# amplificadorAudio.net
KiCad netlist of a schematic drawn in Altium Designer
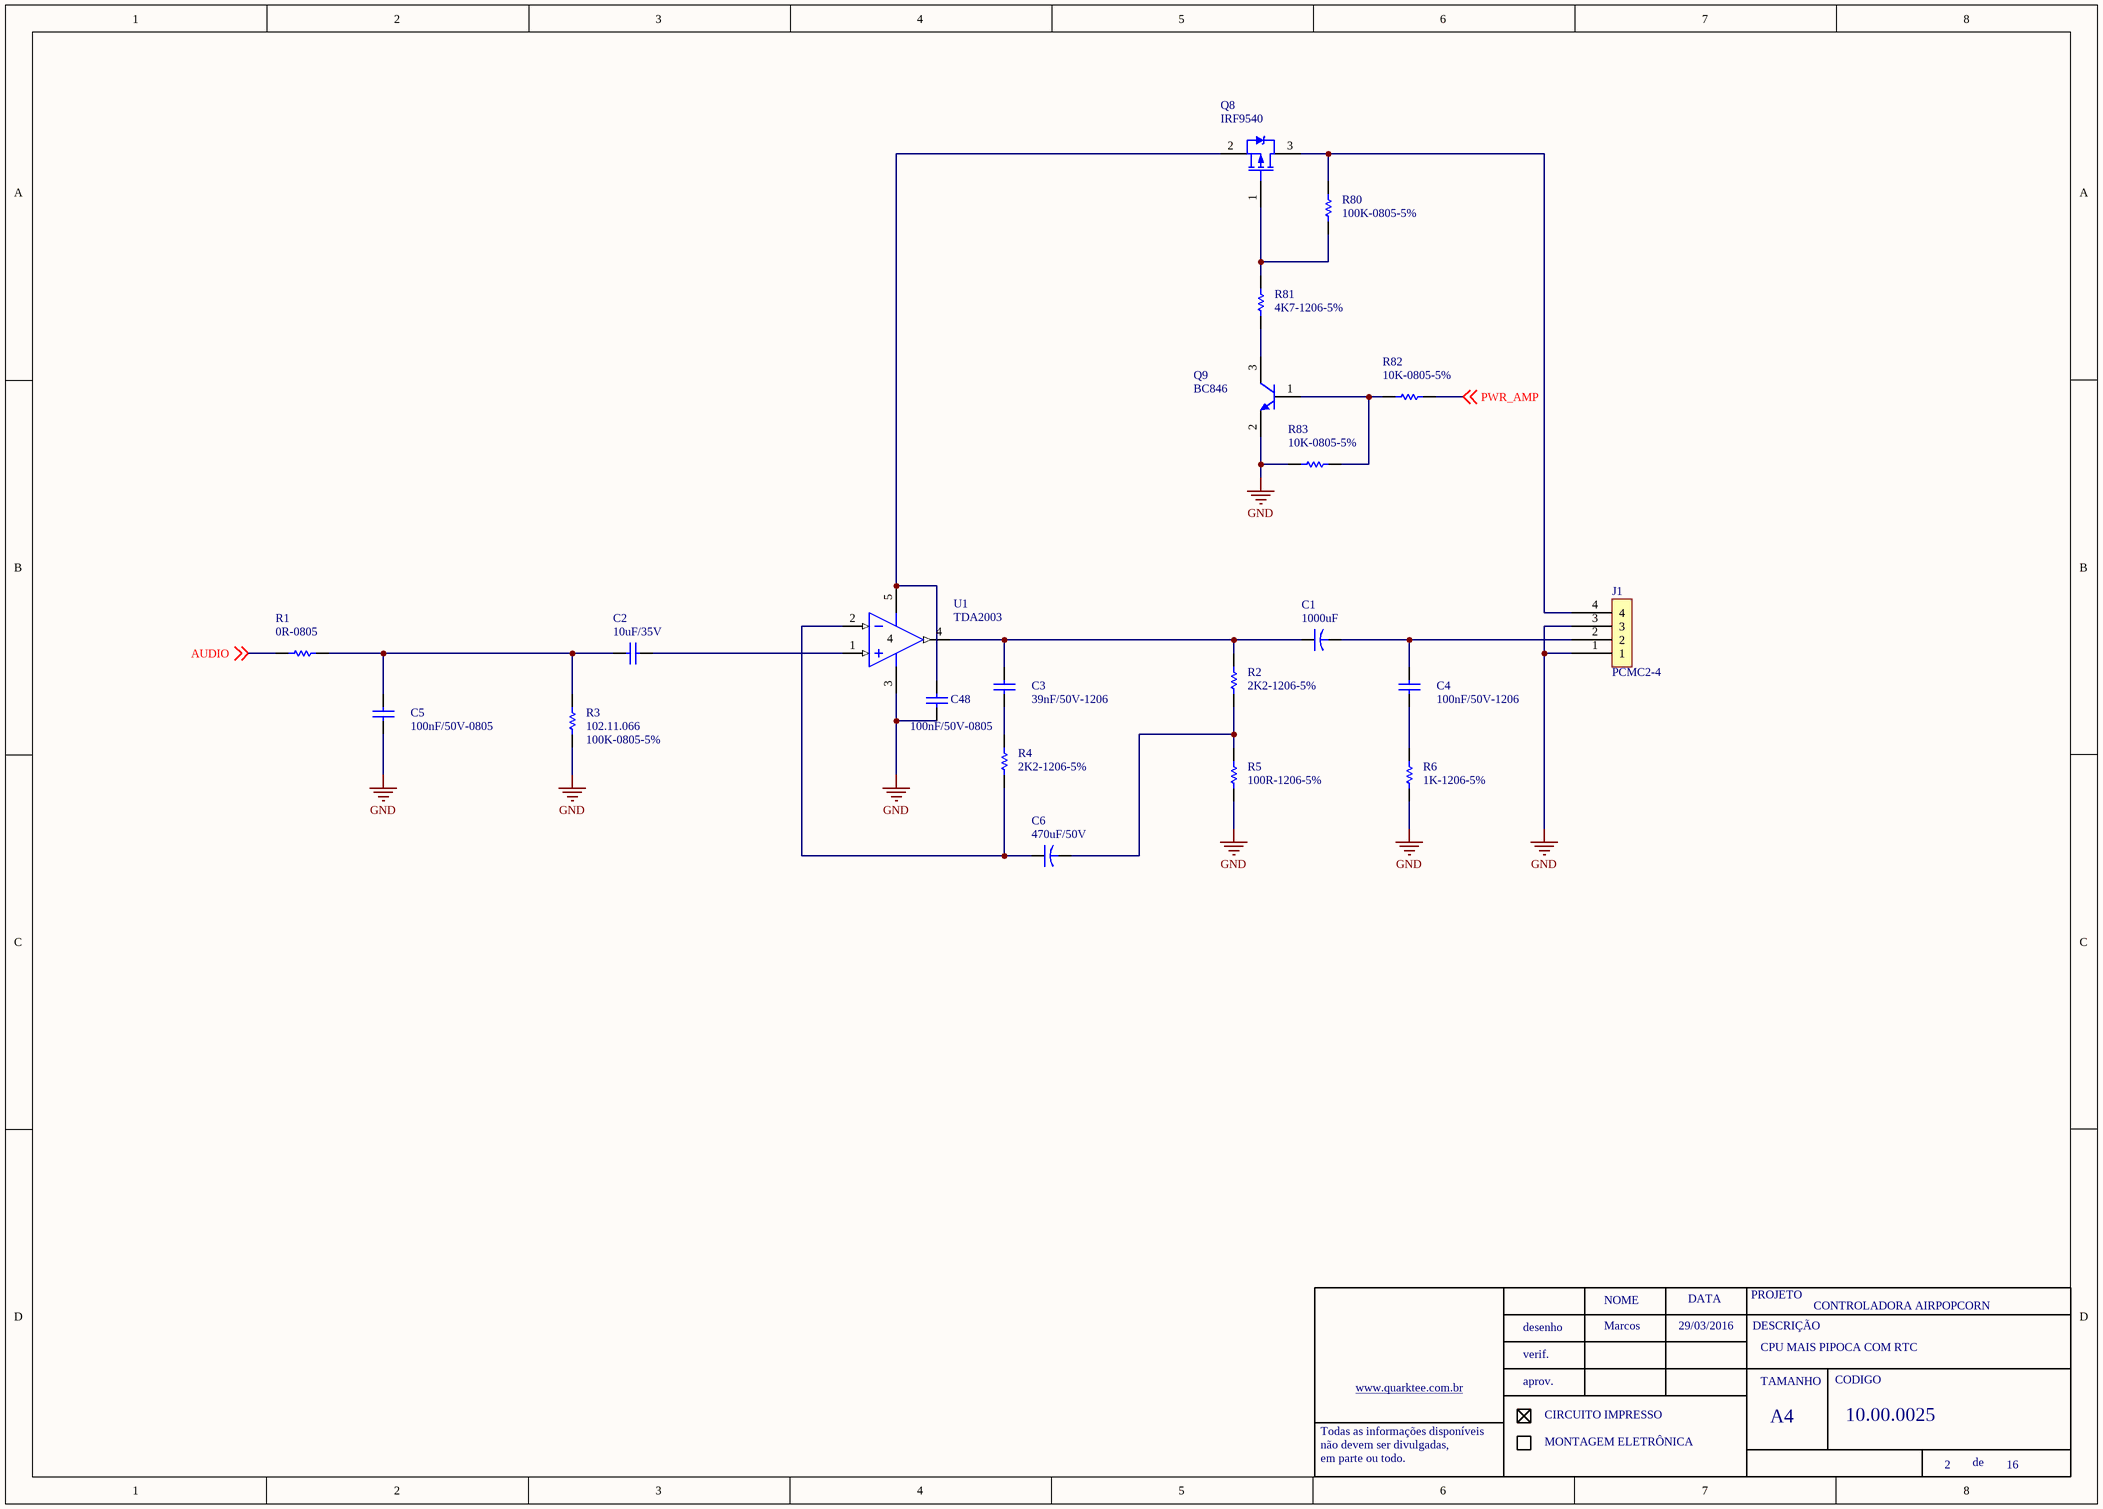
[diagram p0: amplificadorAudio.SchDoc]

(export (version "E")
  (design (tool "Eeschema 10.0.6"))
  (components
    (comp (ref "C1")
      (value "1000uF")
      (footprint "CAP 10X5")
      (description "470uF/50V")
      (libsource (lib "AquinoLib") (part "470uF/50V"))
    )
    (comp (ref "C2")
      (value "10uF/35V")
      (footprint "CAP POL 5x11mm")
      (description "10uF/35V-tantalo-2413")
      (libsource (lib "AquinoLib") (part "10uF/35V-tantalo-2413"))
    )
    (comp (ref "C3")
      (value "39nF/50V-1206")
      (footprint "1206-REVISADO O")
      (description "100nF/50-0805-NPO")
      (libsource (lib "AquinoLib") (part "100nF/50-0805-NPO"))
    )
    (comp (ref "C4")
      (value "100nF/50V-1206")
      (footprint "1206-REVISADO O")
      (description "100nF/50-0805-NPO")
      (libsource (lib "AquinoLib") (part "100nF/50-0805-NPO"))
    )
    (comp (ref "C5")
      (value "100nF/50V-0805")
      (footprint "0805-REVISADO O")
      (description "100nF/50-0805-NPO")
      (libsource (lib "AquinoLib") (part "100nF/50-0805-NPO"))
    )
    (comp (ref "C6")
      (value "470uF/50V")
      (footprint "CAP 10X5")
      (libsource (lib "AquinoLib") (part "470uF/50V"))
    )
    (comp (ref "C48")
      (value "100nF/50V-0805")
      (footprint "0805-REVISADO O")
      (description "100nF/50-0805-NPO")
      (libsource (lib "AquinoLib") (part "100nF/50-0805-NPO"))
    )
    (comp (ref "J1") (value "PCMC2-4") (footprint "PCMC2-4") (libsource (lib "AquinoLib") (part "PCMC2-4")))
    (comp (ref "Q8")
      (value "IRF9540")
      (footprint "TO220-3 EM PÉ")
      (libsource (lib "ChaveDigital3") (part "IRF9540"))
    )
    (comp (ref "Q9")
      (value "BC846")
      (footprint "SOT23 - REVISAD")
      (description "BC846L")
      (libsource (lib "AquinoLib") (part "BC846"))
    )
    (comp (ref "R1")
      (value "0R-0805")
      (footprint "0805-REVISADO O")
      (description "1K-0805-5%")
      (libsource (lib "AquinoLib") (part "1K-0805-5%"))
    )
    (comp (ref "R2")
      (value "2K2-1206-5%")
      (footprint "1206-REVISADO O")
      (description "390R-2512-5%")
      (libsource (lib "AquinoLib") (part "390R-2512-5%"))
    )
    (comp (ref "R3")
      (value "100K-0805-5%")
      (footprint "0805-REVISADO O")
      (fields (field (name "ERP") "102.11.066"))
      (libsource (lib "AquinoLib") (part "100K-0805-5%"))
    )
    (comp (ref "R4")
      (value "2K2-1206-5%")
      (footprint "1206-REVISADO O")
      (description "390R-2512-5%")
      (libsource (lib "AquinoLib") (part "390R-2512-5%"))
    )
    (comp (ref "R5")
      (value "100R-1206-5%")
      (footprint "1206-REVISADO O")
      (description "390R-2512-5%")
      (libsource (lib "AquinoLib") (part "390R-2512-5%"))
    )
    (comp (ref "R6")
      (value "1K-1206-5%")
      (footprint "1206-REVISADO O")
      (description "390R-2512-5%")
      (libsource (lib "AquinoLib") (part "390R-2512-5%"))
    )
    (comp (ref "R80")
      (value "100K-0805-5%")
      (footprint "0805-REVISADO O")
      (description "100K-0805")
      (libsource (lib "ChaveDigital3") (part "RES 100K-0805"))
    )
    (comp (ref "R81")
      (value "4K7-1206-5%")
      (footprint "1206-REVISADO O")
      (libsource (lib "AquinoLib") (part "4K7-1206-5%"))
    )
    (comp (ref "R82")
      (value "10K-0805-5%")
      (footprint "0805-REVISADO O")
      (libsource (lib "AquinoLib") (part "10K-0805-5%"))
    )
    (comp (ref "R83")
      (value "10K-0805-5%")
      (footprint "0805-REVISADO O")
      (libsource (lib "AquinoLib") (part "10K-0805-5%"))
    )
    (comp (ref "U1")
      (value "TDA2003")
      (footprint "PENTAWATT V")
      (libsource (lib "AquinoLib") (part "TDA2003"))
    )
  )
  (nets
    (net (code "1") (name "AUDIO") (class "Default")
      (node (ref "R1") (pin "1") (pinfunction "1_1") (pintype "passive"))
    )
    (net (code "2") (name "GND") (class "Default")
      (node (ref "C48") (pin "1") (pinfunction "1_1") (pintype "passive"))
      (node (ref "C5") (pin "1") (pinfunction "1_1") (pintype "passive"))
      (node (ref "J1") (pin "1") (pinfunction "1_1") (pintype "passive"))
      (node (ref "J1") (pin "3") (pinfunction "3_3") (pintype "passive"))
      (node (ref "Q9") (pin "2") (pinfunction "E_2") (pintype "passive"))
      (node (ref "R3") (pin "1") (pinfunction "1_1") (pintype "passive"))
      (node (ref "R5") (pin "2") (pinfunction "2_2") (pintype "passive"))
      (node (ref "R6") (pin "2") (pinfunction "2_2") (pintype "passive"))
      (node (ref "R83") (pin "1") (pinfunction "1_1") (pintype "passive"))
      (node (ref "U1") (pin "3") (pinfunction "GND_3") (pintype "power_in"))
    )
    (net (code "3") (name "Net-(C1-Pad2)") (class "Default")
      (node (ref "C1") (pin "2") (pinfunction "2_2") (pintype "passive"))
      (node (ref "C4") (pin "2") (pinfunction "2_2") (pintype "passive"))
      (node (ref "J1") (pin "2") (pinfunction "2_2") (pintype "passive"))
    )
    (net (code "4") (name "Net-(C2-Pad1)") (class "Default")
      (node (ref "C2") (pin "1") (pinfunction "1_1") (pintype "passive"))
      (node (ref "C5") (pin "2") (pinfunction "2_2") (pintype "passive"))
      (node (ref "R1") (pin "2") (pinfunction "2_2") (pintype "passive"))
      (node (ref "R3") (pin "2") (pinfunction "2_2") (pintype "passive"))
    )
    (net (code "5") (name "Net-(C3-Pad1)") (class "Default")
      (node (ref "C3") (pin "1") (pinfunction "1_1") (pintype "passive"))
      (node (ref "R4") (pin "1") (pinfunction "1_1") (pintype "passive"))
    )
    (net (code "6") (name "Net-(C4-Pad1)") (class "Default")
      (node (ref "C4") (pin "1") (pinfunction "1_1") (pintype "passive"))
      (node (ref "R6") (pin "1") (pinfunction "1_1") (pintype "passive"))
    )
    (net (code "7") (name "Net-(C6-Pad2)") (class "Default")
      (node (ref "C6") (pin "2") (pinfunction "2_2") (pintype "passive"))
      (node (ref "R2") (pin "2") (pinfunction "2_2") (pintype "passive"))
      (node (ref "R5") (pin "1") (pinfunction "1_1") (pintype "passive"))
    )
    (net (code "8") (name "Net-(Q8-DRENO)") (class "Default")
      (node (ref "C48") (pin "2") (pinfunction "2_2") (pintype "passive"))
      (node (ref "Q8") (pin "2") (pinfunction "DRENO_2") (pintype "passive"))
      (node (ref "U1") (pin "5") (pinfunction "V+_5") (pintype "power_in"))
    )
    (net (code "9") (name "Net-(Q8-GATE)") (class "Default")
      (node (ref "Q8") (pin "1") (pinfunction "GATE_1") (pintype "passive"))
      (node (ref "R80") (pin "1") (pinfunction "1_1") (pintype "passive"))
      (node (ref "R81") (pin "2") (pinfunction "2_2") (pintype "passive"))
    )
    (net (code "10") (name "Net-(Q8-SOURCE)") (class "Default")
      (node (ref "J1") (pin "4") (pinfunction "4_4") (pintype "passive"))
      (node (ref "Q8") (pin "3") (pinfunction "SOURCE_3") (pintype "passive"))
      (node (ref "R80") (pin "2") (pinfunction "2_2") (pintype "passive"))
    )
    (net (code "11") (name "Net-(Q9-B)") (class "Default")
      (node (ref "Q9") (pin "1") (pinfunction "B_1") (pintype "passive"))
      (node (ref "R82") (pin "1") (pinfunction "1_1") (pintype "passive"))
      (node (ref "R83") (pin "2") (pinfunction "2_2") (pintype "passive"))
    )
    (net (code "12") (name "Net-(Q9-C)") (class "Default")
      (node (ref "Q9") (pin "3") (pinfunction "C_3") (pintype "passive"))
      (node (ref "R81") (pin "1") (pinfunction "1_1") (pintype "passive"))
    )
    (net (code "13") (name "Net-(U1-IN+)") (class "Default")
      (node (ref "C2") (pin "2") (pinfunction "2_2") (pintype "passive"))
      (node (ref "U1") (pin "1") (pinfunction "IN+_1") (pintype "input"))
    )
    (net (code "14") (name "Net-(U1-IN-)") (class "Default")
      (node (ref "C6") (pin "1") (pinfunction "1_1") (pintype "passive"))
      (node (ref "R4") (pin "2") (pinfunction "2_2") (pintype "passive"))
      (node (ref "U1") (pin "2") (pinfunction "IN-_2") (pintype "input"))
    )
    (net (code "15") (name "Net-(U1-OUT)") (class "Default")
      (node (ref "C1") (pin "1") (pinfunction "1_1") (pintype "passive"))
      (node (ref "C3") (pin "2") (pinfunction "2_2") (pintype "passive"))
      (node (ref "R2") (pin "1") (pinfunction "1_1") (pintype "passive"))
      (node (ref "U1") (pin "4") (pinfunction "OUT_4") (pintype "output"))
    )
    (net (code "16") (name "PWR_AMP") (class "Default")
      (node (ref "R82") (pin "2") (pinfunction "2_2") (pintype "passive"))
    )
  )
)
